# bqZUM_Bluetooth.net
KiCad netlist of a schematic drawn in Altium Designer
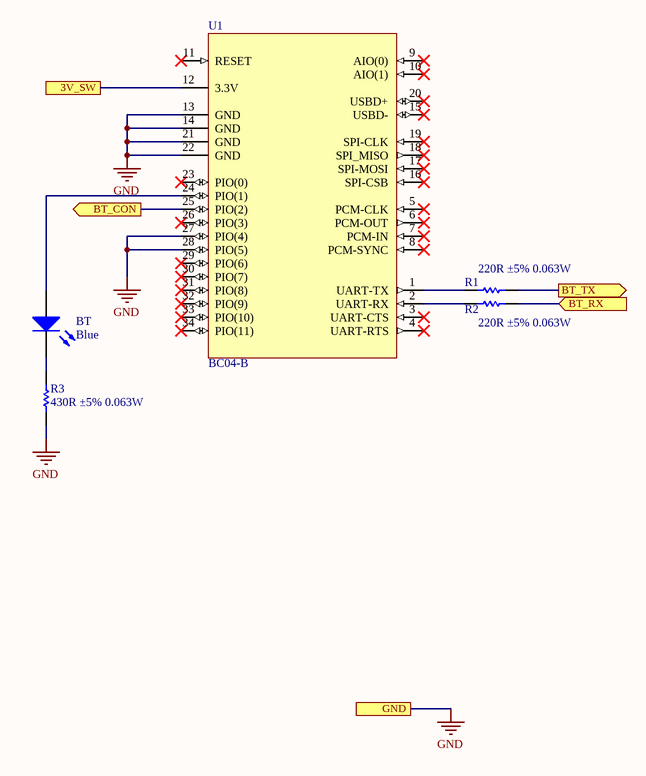
[diagram p0: bqZUM_Bluetooth.SchDoc]

(export (version "E")
  (design (tool "Eeschema 10.0.6"))
  (components
    (comp (ref "BT")
      (value "Blue")
      (footprint "LED0603")
      (description "Light Emitting Diode")
      (fields (field (name "PART NUMBER") "LTST-C194TBKT") (field (name "MANUFACTURER") "Lite-On"))
      (libsource (lib "Optoelectronics") (part "LED"))
    )
    (comp (ref "R1")
      (value "220R ±5% 0.063W")
      (footprint "R0402")
      (description "Resistor")
      (fields (field (name "TOLERANCE") "±5%") (field (name "POWER") "0.063W"))
      (libsource (lib "Pasives_Resistor_SMD") (part "Resistor"))
    )
    (comp (ref "R2")
      (value "220R ±5% 0.063W")
      (footprint "R0402")
      (description "Resistor")
      (fields (field (name "TOLERANCE") "±5%") (field (name "POWER") "0.063W"))
      (libsource (lib "Pasives_Resistor_SMD") (part "Resistor"))
    )
    (comp (ref "R3")
      (value "430R ±5% 0.063W")
      (footprint "R0402")
      (description "Resistor")
      (fields (field (name "TOLERANCE") "±5%") (field (name "POWER") "0.063W"))
      (libsource (lib "Pasives_Resistor_SMD") (part "Resistor"))
    )
    (comp (ref "U1")
      (value "BC04-B")
      (footprint "BC04-B")
      (description "BC04-B Bluetooth module")
      (fields (field (name "MANUFACTURER") "Bolutek"))
      (libsource (lib "Modules") (part "BC04-B"))
    )
  )
  (nets
    (net (code "1") (name "/3V_SW") (class "Default")
      (node (ref "U1") (pin "12") (pinfunction "3.3V_12") (pintype "power_in"))
    )
    (net (code "2") (name "/BT_CON") (class "Default")
      (node (ref "U1") (pin "25") (pinfunction "PIO(2)_25") (pintype "bidirectional"))
    )
    (net (code "3") (name "/BT_RX") (class "Default")
      (node (ref "R2") (pin "2") (pinfunction "2_2") (pintype "passive"))
    )
    (net (code "4") (name "/BT_TX") (class "Default")
      (node (ref "R1") (pin "2") (pinfunction "2_2") (pintype "passive"))
    )
    (net (code "5") (name "GND") (class "Default")
      (node (ref "R3") (pin "1") (pinfunction "1_1") (pintype "passive"))
      (node (ref "U1") (pin "13") (pinfunction "GND_13") (pintype "power_in"))
      (node (ref "U1") (pin "14") (pinfunction "GND_14") (pintype "power_in"))
      (node (ref "U1") (pin "21") (pinfunction "GND_21") (pintype "power_in"))
      (node (ref "U1") (pin "22") (pinfunction "GND_22") (pintype "power_in"))
      (node (ref "U1") (pin "27") (pinfunction "PIO(4)_27") (pintype "bidirectional"))
      (node (ref "U1") (pin "28") (pinfunction "PIO(5)_28") (pintype "bidirectional"))
    )
    (net (code "6") (name "Net-(BT-PadK)") (class "Default")
      (node (ref "BT") (pin "K") (pinfunction "K_K") (pintype "passive"))
      (node (ref "R3") (pin "2") (pinfunction "2_2") (pintype "passive"))
    )
    (net (code "7") (name "Net-(U1-PIO(1))") (class "Default")
      (node (ref "BT") (pin "A") (pinfunction "A_A") (pintype "passive"))
      (node (ref "U1") (pin "24") (pinfunction "PIO(1)_24") (pintype "bidirectional"))
    )
    (net (code "8") (name "Net-(U1-UART-RX)") (class "Default")
      (node (ref "R2") (pin "1") (pinfunction "1_1") (pintype "passive"))
      (node (ref "U1") (pin "2") (pinfunction "UART-RX_2") (pintype "input"))
    )
    (net (code "9") (name "Net-(U1-UART-TX)") (class "Default")
      (node (ref "R1") (pin "1") (pinfunction "1_1") (pintype "passive"))
      (node (ref "U1") (pin "1") (pinfunction "UART-TX_1") (pintype "output"))
    )
    (net (code "10") (name "unconnected-(U1-AIO(0)-Pad9)") (class "Default")
      (node (ref "U1") (pin "9") (pinfunction "AIO(0)_9") (pintype "input+no_connect"))
    )
    (net (code "11") (name "unconnected-(U1-AIO(1)-Pad10)") (class "Default")
      (node (ref "U1") (pin "10") (pinfunction "AIO(1)_10") (pintype "input+no_connect"))
    )
    (net (code "12") (name "unconnected-(U1-PCM-CLK-Pad5)") (class "Default")
      (node (ref "U1") (pin "5") (pinfunction "PCM-CLK_5") (pintype "input+no_connect"))
    )
    (net (code "13") (name "unconnected-(U1-PCM-IN-Pad7)") (class "Default")
      (node (ref "U1") (pin "7") (pinfunction "PCM-IN_7") (pintype "input+no_connect"))
    )
    (net (code "14") (name "unconnected-(U1-PCM-OUT-Pad6)") (class "Default")
      (node (ref "U1") (pin "6") (pinfunction "PCM-OUT_6") (pintype "output+no_connect"))
    )
    (net (code "15") (name "unconnected-(U1-PCM-SYNC-Pad8)") (class "Default")
      (node (ref "U1") (pin "8") (pinfunction "PCM-SYNC_8") (pintype "input+no_connect"))
    )
    (net (code "16") (name "unconnected-(U1-PIO(0)-Pad23)") (class "Default")
      (node (ref "U1") (pin "23") (pinfunction "PIO(0)_23") (pintype "bidirectional+no_connect"))
    )
    (net (code "17") (name "unconnected-(U1-PIO(3)-Pad26)") (class "Default")
      (node (ref "U1") (pin "26") (pinfunction "PIO(3)_26") (pintype "bidirectional+no_connect"))
    )
    (net (code "18") (name "unconnected-(U1-PIO(6)-Pad29)") (class "Default")
      (node (ref "U1") (pin "29") (pinfunction "PIO(6)_29") (pintype "bidirectional+no_connect"))
    )
    (net (code "19") (name "unconnected-(U1-PIO(7)-Pad30)") (class "Default")
      (node (ref "U1") (pin "30") (pinfunction "PIO(7)_30") (pintype "bidirectional+no_connect"))
    )
    (net (code "20") (name "unconnected-(U1-PIO(8)-Pad31)") (class "Default")
      (node (ref "U1") (pin "31") (pinfunction "PIO(8)_31") (pintype "bidirectional+no_connect"))
    )
    (net (code "21") (name "unconnected-(U1-PIO(9)-Pad32)") (class "Default")
      (node (ref "U1") (pin "32") (pinfunction "PIO(9)_32") (pintype "bidirectional+no_connect"))
    )
    (net (code "22") (name "unconnected-(U1-PIO(10)-Pad33)") (class "Default")
      (node (ref "U1") (pin "33") (pinfunction "PIO(10)_33") (pintype "bidirectional+no_connect"))
    )
    (net (code "23") (name "unconnected-(U1-PIO(11)-Pad34)") (class "Default")
      (node (ref "U1") (pin "34") (pinfunction "PIO(11)_34") (pintype "bidirectional+no_connect"))
    )
    (net (code "24") (name "unconnected-(U1-RESET-Pad11)") (class "Default")
      (node (ref "U1") (pin "11") (pinfunction "RESET_11") (pintype "input+no_connect"))
    )
    (net (code "25") (name "unconnected-(U1-SPI-CLK-Pad19)") (class "Default")
      (node (ref "U1") (pin "19") (pinfunction "SPI-CLK_19") (pintype "input+no_connect"))
    )
    (net (code "26") (name "unconnected-(U1-SPI-CSB-Pad16)") (class "Default")
      (node (ref "U1") (pin "16") (pinfunction "SPI-CSB_16") (pintype "input+no_connect"))
    )
    (net (code "27") (name "unconnected-(U1-SPI-MOSI-Pad17)") (class "Default")
      (node (ref "U1") (pin "17") (pinfunction "SPI-MOSI_17") (pintype "input+no_connect"))
    )
    (net (code "28") (name "unconnected-(U1-SPI_MISO-Pad18)") (class "Default")
      (node (ref "U1") (pin "18") (pinfunction "SPI_MISO_18") (pintype "output+no_connect"))
    )
    (net (code "29") (name "unconnected-(U1-UART-CTS-Pad3)") (class "Default")
      (node (ref "U1") (pin "3") (pinfunction "UART-CTS_3") (pintype "input+no_connect"))
    )
    (net (code "30") (name "unconnected-(U1-UART-RTS-Pad4)") (class "Default")
      (node (ref "U1") (pin "4") (pinfunction "UART-RTS_4") (pintype "output+no_connect"))
    )
    (net (code "31") (name "unconnected-(U1-USBD+-Pad20)") (class "Default")
      (node (ref "U1") (pin "20") (pinfunction "USBD+_20") (pintype "bidirectional+no_connect"))
    )
    (net (code "32") (name "unconnected-(U1-USBD--Pad15)") (class "Default")
      (node (ref "U1") (pin "15") (pinfunction "USBD-_15") (pintype "bidirectional+no_connect"))
    )
  )
)
